# Sheet2.net
KiCad netlist of a schematic drawn in Altium Designer
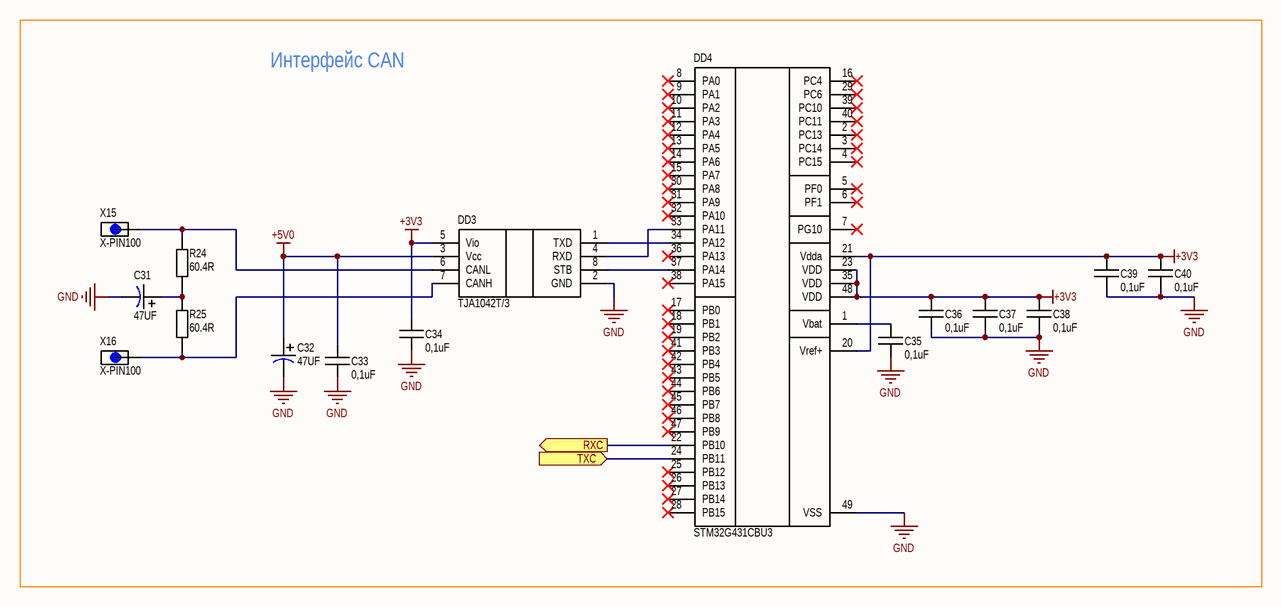
[diagram p0: Sheet2.SchDoc]

(export (version "E")
  (design (tool "Eeschema 10.0.6"))
  (components
    (comp (ref "C31")
      (value "47UF")
      (footprint "B1411_3528")
      (description "CP1411B 47UF 6V3")
      (fields
        (field (name "PART NUMBER") "SMD CAP TANTAL 47uF ±10% 6V3 1411B")
        (field (name "ADDED_BY") "ridel_av@teslatec.ru")
      )
      (libsource (lib "81801_1") (part "CP1411B-47UF"))
    )
    (comp (ref "C32")
      (value "47UF")
      (footprint "B1411_3528")
      (description "CP1411B 47UF 6V3")
      (fields
        (field (name "PART NUMBER") "SMD CAP TANTAL 47uF ±10% 6V3 1411B")
        (field (name "ADDED_BY") "ridel_av@teslatec.ru")
      )
      (libsource (lib "81801_1") (part "CP1411B-47UF"))
    )
    (comp (ref "C33")
      (value "0,1uF")
      (footprint "0805C")
      (description "C0805 0,1uF")
      (fields
        (field (name "PART NUMBER") "SMD CAP CER 0.1uF ±10% 25V X7R 0805")
        (field (name "ADDED_BY") "ridel_av@teslatec.ru")
      )
      (libsource (lib "81801_1") (part "C0805-0,1uF"))
    )
    (comp (ref "C34")
      (value "0,1uF")
      (footprint "0805C")
      (description "C0805 0,1uF")
      (fields
        (field (name "PART NUMBER") "SMD CAP CER 0.1uF ±10% 25V X7R 0805")
        (field (name "ADDED_BY") "ridel_av@teslatec.ru")
      )
      (libsource (lib "81801_1") (part "C0805-0,1uF"))
    )
    (comp (ref "C35")
      (value "0,1uF")
      (footprint "0805C")
      (description "C0805 0,1uF")
      (fields
        (field (name "PART NUMBER") "SMD CAP CER 0.1uF ±10% 25V X7R 0805")
        (field (name "ADDED_BY") "ridel_av@teslatec.ru")
      )
      (libsource (lib "81801_1") (part "C0805-0,1uF"))
    )
    (comp (ref "C36")
      (value "0,1uF")
      (footprint "0805C")
      (description "C0805 0,1uF")
      (fields
        (field (name "PART NUMBER") "SMD CAP CER 0.1uF ±10% 25V X7R 0805")
        (field (name "ADDED_BY") "ridel_av@teslatec.ru")
      )
      (libsource (lib "81801_1") (part "C0805-0,1uF"))
    )
    (comp (ref "C37")
      (value "0,1uF")
      (footprint "0805C")
      (description "C0805 0,1uF")
      (fields
        (field (name "PART NUMBER") "SMD CAP CER 0.1uF ±10% 25V X7R 0805")
        (field (name "ADDED_BY") "ridel_av@teslatec.ru")
      )
      (libsource (lib "81801_1") (part "C0805-0,1uF"))
    )
    (comp (ref "C38")
      (value "0,1uF")
      (footprint "0805C")
      (description "C0805 0,1uF")
      (fields
        (field (name "PART NUMBER") "SMD CAP CER 0.1uF ±10% 25V X7R 0805")
        (field (name "ADDED_BY") "ridel_av@teslatec.ru")
      )
      (libsource (lib "81801_1") (part "C0805-0,1uF"))
    )
    (comp (ref "C39")
      (value "0,1uF")
      (footprint "0805C")
      (description "C0805 0,1uF")
      (fields
        (field (name "PART NUMBER") "SMD CAP CER 0.1uF ±10% 25V X7R 0805")
        (field (name "ADDED_BY") "ridel_av@teslatec.ru")
      )
      (libsource (lib "81801_1") (part "C0805-0,1uF"))
    )
    (comp (ref "C40")
      (value "0,1uF")
      (footprint "0805C")
      (description "C0805 0,1uF")
      (fields
        (field (name "PART NUMBER") "SMD CAP CER 0.1uF ±10% 25V X7R 0805")
        (field (name "ADDED_BY") "ridel_av@teslatec.ru")
      )
      (libsource (lib "81801_1") (part "C0805-0,1uF"))
    )
    (comp (ref "DD3")
      (value "TJA1042T/3")
      (footprint "SOIC-8")
      (description "High-speed CAN transceiver with Standby mode")
      (fields (field (name "ADDED_BY") "dolgopolova_ia@teslatec.ru"))
      (libsource (lib "81801_1") (part "TJA1042T/3"))
    )
    (comp (ref "DD4")
      (value "STM32G431CBU3")
      (footprint "TQFP-64")
      (description "Arm Cortex-M4 32b MCU+FPU, 170 MHz / 213 DMIPS, 128 KB Flash")
      (fields (field (name "ADDED_BY") "ridel_av@teslatec.ru"))
      (libsource (lib "81801_1") (part "STM32G431CBU3"))
    )
    (comp (ref "R24")
      (value "60.4R")
      (footprint "R0805")
      (description "R0805 SMD 60.4R OHM 1% ±100ppm/°C")
      (fields
        (field (name "PART NUMBER") "SMD RES 60.4 OHM 1% ±100ppm/°C 0805")
        (field (name "ADDED_BY") "ridel_av@teslatec.ru")
      )
      (libsource (lib "81801_1") (part "R0805-60.4R"))
    )
    (comp (ref "R25")
      (value "60.4R")
      (footprint "R0805")
      (description "R0805 SMD 60.4R OHM 1% ±100ppm/°C")
      (fields
        (field (name "PART NUMBER") "SMD RES 60.4 OHM 1% ±100ppm/°C 0805")
        (field (name "ADDED_BY") "ridel_av@teslatec.ru")
      )
      (libsource (lib "81801_1") (part "R0805-60.4R"))
    )
    (comp (ref "X15")
      (value "X-PIN100")
      (footprint "Xpin100")
      (fields (field (name "ADDED_BY") "ridel_av@teslatec.ru"))
      (libsource (lib "81801_1") (part "X-PIN100"))
    )
    (comp (ref "X16")
      (value "X-PIN100")
      (footprint "Xpin100")
      (fields (field (name "ADDED_BY") "ridel_av@teslatec.ru"))
      (libsource (lib "81801_1") (part "X-PIN100"))
    )
  )
  (nets
    (net (code "1") (name "+3V3") (class "Default")
      (node (ref "C34") (pin "1") (pinfunction "1_1") (pintype "passive"))
      (node (ref "C36") (pin "1") (pinfunction "1_1") (pintype "passive"))
      (node (ref "C37") (pin "1") (pinfunction "1_1") (pintype "passive"))
      (node (ref "C38") (pin "1") (pinfunction "1_1") (pintype "passive"))
      (node (ref "C39") (pin "1") (pinfunction "1_1") (pintype "passive"))
      (node (ref "C40") (pin "1") (pinfunction "1_1") (pintype "passive"))
      (node (ref "DD3") (pin "5") (pinfunction "Vio_5") (pintype "passive"))
      (node (ref "DD4") (pin "20") (pinfunction "Vref+_20") (pintype "passive"))
      (node (ref "DD4") (pin "21") (pinfunction "Vdda_21") (pintype "passive"))
      (node (ref "DD4") (pin "23") (pinfunction "VDD_23") (pintype "passive"))
      (node (ref "DD4") (pin "35") (pinfunction "VDD_35") (pintype "passive"))
      (node (ref "DD4") (pin "48") (pinfunction "VDD_48") (pintype "passive"))
    )
    (net (code "2") (name "+5V0") (class "Default")
      (node (ref "C32") (pin "1") (pinfunction "1_1") (pintype "passive"))
      (node (ref "C33") (pin "1") (pinfunction "1_1") (pintype "passive"))
      (node (ref "DD3") (pin "3") (pinfunction "Vcc_3") (pintype "passive"))
    )
    (net (code "3") (name "/RXC") (class "Default")
      (node (ref "DD4") (pin "22") (pinfunction "PB10_22") (pintype "passive"))
    )
    (net (code "4") (name "/TXC") (class "Default")
      (node (ref "DD4") (pin "24") (pinfunction "PB11_24") (pintype "passive"))
    )
    (net (code "5") (name "GND") (class "Default")
      (node (ref "C31") (pin "2") (pinfunction "2_2") (pintype "passive"))
      (node (ref "C32") (pin "2") (pinfunction "2_2") (pintype "passive"))
      (node (ref "C33") (pin "2") (pinfunction "2_2") (pintype "passive"))
      (node (ref "C34") (pin "2") (pinfunction "2_2") (pintype "passive"))
      (node (ref "C35") (pin "2") (pinfunction "2_2") (pintype "passive"))
      (node (ref "C36") (pin "2") (pinfunction "2_2") (pintype "passive"))
      (node (ref "C37") (pin "2") (pinfunction "2_2") (pintype "passive"))
      (node (ref "C38") (pin "2") (pinfunction "2_2") (pintype "passive"))
      (node (ref "C39") (pin "2") (pinfunction "2_2") (pintype "passive"))
      (node (ref "C40") (pin "2") (pinfunction "2_2") (pintype "passive"))
      (node (ref "DD3") (pin "2") (pinfunction "GND_2") (pintype "passive"))
      (node (ref "DD4") (pin "49") (pinfunction "VSS_49") (pintype "passive"))
    )
    (net (code "6") (name "Net-(C31-Pad1)") (class "Default")
      (node (ref "C31") (pin "1") (pinfunction "1_1") (pintype "passive"))
      (node (ref "R24") (pin "1") (pinfunction "1_1") (pintype "passive"))
      (node (ref "R25") (pin "2") (pinfunction "2_2") (pintype "passive"))
    )
    (net (code "7") (name "Net-(DD3-CANH)") (class "Default")
      (node (ref "DD3") (pin "7") (pinfunction "CANH_7") (pintype "passive"))
      (node (ref "R25") (pin "1") (pinfunction "1_1") (pintype "passive"))
      (node (ref "X16") (pin "1") (pintype "passive"))
    )
    (net (code "8") (name "Net-(DD3-CANL)") (class "Default")
      (node (ref "DD3") (pin "6") (pinfunction "CANL_6") (pintype "passive"))
      (node (ref "R24") (pin "2") (pinfunction "2_2") (pintype "passive"))
      (node (ref "X15") (pin "1") (pintype "passive"))
    )
    (net (code "9") (name "Net-(DD3-RXD)") (class "Default")
      (node (ref "DD3") (pin "4") (pinfunction "RXD_4") (pintype "passive"))
      (node (ref "DD4") (pin "33") (pinfunction "PA11_33") (pintype "passive"))
    )
    (net (code "10") (name "Net-(DD3-STB)") (class "Default")
      (node (ref "DD3") (pin "8") (pinfunction "STB_8") (pintype "passive"))
      (node (ref "DD4") (pin "37") (pinfunction "PA14_37") (pintype "passive"))
    )
    (net (code "11") (name "Net-(DD3-TXD)") (class "Default")
      (node (ref "DD3") (pin "1") (pinfunction "TXD_1") (pintype "passive"))
      (node (ref "DD4") (pin "34") (pinfunction "PA12_34") (pintype "passive"))
    )
    (net (code "12") (name "Net-(DD4-Vbat)") (class "Default")
      (node (ref "C35") (pin "1") (pinfunction "1_1") (pintype "passive"))
      (node (ref "DD4") (pin "1") (pinfunction "Vbat_1") (pintype "passive"))
    )
    (net (code "13") (name "unconnected-(DD4-PA0-Pad8)") (class "Default")
      (node (ref "DD4") (pin "8") (pinfunction "PA0_8") (pintype "passive+no_connect"))
    )
    (net (code "14") (name "unconnected-(DD4-PA1-Pad9)") (class "Default")
      (node (ref "DD4") (pin "9") (pinfunction "PA1_9") (pintype "passive+no_connect"))
    )
    (net (code "15") (name "unconnected-(DD4-PA2-Pad10)") (class "Default")
      (node (ref "DD4") (pin "10") (pinfunction "PA2_10") (pintype "passive+no_connect"))
    )
    (net (code "16") (name "unconnected-(DD4-PA3-Pad11)") (class "Default")
      (node (ref "DD4") (pin "11") (pinfunction "PA3_11") (pintype "passive+no_connect"))
    )
    (net (code "17") (name "unconnected-(DD4-PA4-Pad12)") (class "Default")
      (node (ref "DD4") (pin "12") (pinfunction "PA4_12") (pintype "passive+no_connect"))
    )
    (net (code "18") (name "unconnected-(DD4-PA5-Pad13)") (class "Default")
      (node (ref "DD4") (pin "13") (pinfunction "PA5_13") (pintype "passive+no_connect"))
    )
    (net (code "19") (name "unconnected-(DD4-PA6-Pad14)") (class "Default")
      (node (ref "DD4") (pin "14") (pinfunction "PA6_14") (pintype "passive+no_connect"))
    )
    (net (code "20") (name "unconnected-(DD4-PA7-Pad15)") (class "Default")
      (node (ref "DD4") (pin "15") (pinfunction "PA7_15") (pintype "passive+no_connect"))
    )
    (net (code "21") (name "unconnected-(DD4-PA8-Pad30)") (class "Default")
      (node (ref "DD4") (pin "30") (pinfunction "PA8_30") (pintype "passive+no_connect"))
    )
    (net (code "22") (name "unconnected-(DD4-PA9-Pad31)") (class "Default")
      (node (ref "DD4") (pin "31") (pinfunction "PA9_31") (pintype "passive+no_connect"))
    )
    (net (code "23") (name "unconnected-(DD4-PA10-Pad32)") (class "Default")
      (node (ref "DD4") (pin "32") (pinfunction "PA10_32") (pintype "passive+no_connect"))
    )
    (net (code "24") (name "unconnected-(DD4-PA13-Pad36)") (class "Default")
      (node (ref "DD4") (pin "36") (pinfunction "PA13_36") (pintype "passive+no_connect"))
    )
    (net (code "25") (name "unconnected-(DD4-PA15-Pad38)") (class "Default")
      (node (ref "DD4") (pin "38") (pinfunction "PA15_38") (pintype "passive+no_connect"))
    )
    (net (code "26") (name "unconnected-(DD4-PB0-Pad17)") (class "Default")
      (node (ref "DD4") (pin "17") (pinfunction "PB0_17") (pintype "passive+no_connect"))
    )
    (net (code "27") (name "unconnected-(DD4-PB1-Pad18)") (class "Default")
      (node (ref "DD4") (pin "18") (pinfunction "PB1_18") (pintype "passive+no_connect"))
    )
    (net (code "28") (name "unconnected-(DD4-PB2-Pad19)") (class "Default")
      (node (ref "DD4") (pin "19") (pinfunction "PB2_19") (pintype "passive+no_connect"))
    )
    (net (code "29") (name "unconnected-(DD4-PB3-Pad41)") (class "Default")
      (node (ref "DD4") (pin "41") (pinfunction "PB3_41") (pintype "passive+no_connect"))
    )
    (net (code "30") (name "unconnected-(DD4-PB4-Pad42)") (class "Default")
      (node (ref "DD4") (pin "42") (pinfunction "PB4_42") (pintype "passive+no_connect"))
    )
    (net (code "31") (name "unconnected-(DD4-PB5-Pad43)") (class "Default")
      (node (ref "DD4") (pin "43") (pinfunction "PB5_43") (pintype "passive+no_connect"))
    )
    (net (code "32") (name "unconnected-(DD4-PB6-Pad44)") (class "Default")
      (node (ref "DD4") (pin "44") (pinfunction "PB6_44") (pintype "passive+no_connect"))
    )
    (net (code "33") (name "unconnected-(DD4-PB7-Pad45)") (class "Default")
      (node (ref "DD4") (pin "45") (pinfunction "PB7_45") (pintype "passive+no_connect"))
    )
    (net (code "34") (name "unconnected-(DD4-PB8-Pad46)") (class "Default")
      (node (ref "DD4") (pin "46") (pinfunction "PB8_46") (pintype "passive+no_connect"))
    )
    (net (code "35") (name "unconnected-(DD4-PB9-Pad47)") (class "Default")
      (node (ref "DD4") (pin "47") (pinfunction "PB9_47") (pintype "passive+no_connect"))
    )
    (net (code "36") (name "unconnected-(DD4-PB12-Pad25)") (class "Default")
      (node (ref "DD4") (pin "25") (pinfunction "PB12_25") (pintype "passive+no_connect"))
    )
    (net (code "37") (name "unconnected-(DD4-PB13-Pad26)") (class "Default")
      (node (ref "DD4") (pin "26") (pinfunction "PB13_26") (pintype "passive+no_connect"))
    )
    (net (code "38") (name "unconnected-(DD4-PB14-Pad27)") (class "Default")
      (node (ref "DD4") (pin "27") (pinfunction "PB14_27") (pintype "passive+no_connect"))
    )
    (net (code "39") (name "unconnected-(DD4-PB15-Pad28)") (class "Default")
      (node (ref "DD4") (pin "28") (pinfunction "PB15_28") (pintype "passive+no_connect"))
    )
    (net (code "40") (name "unconnected-(DD4-PC4-Pad16)") (class "Default")
      (node (ref "DD4") (pin "16") (pinfunction "PC4_16") (pintype "passive+no_connect"))
    )
    (net (code "41") (name "unconnected-(DD4-PC6-Pad29)") (class "Default")
      (node (ref "DD4") (pin "29") (pinfunction "PC6_29") (pintype "passive+no_connect"))
    )
    (net (code "42") (name "unconnected-(DD4-PC10-Pad39)") (class "Default")
      (node (ref "DD4") (pin "39") (pinfunction "PC10_39") (pintype "passive+no_connect"))
    )
    (net (code "43") (name "unconnected-(DD4-PC11-Pad40)") (class "Default")
      (node (ref "DD4") (pin "40") (pinfunction "PC11_40") (pintype "passive+no_connect"))
    )
    (net (code "44") (name "unconnected-(DD4-PC13-Pad2)") (class "Default")
      (node (ref "DD4") (pin "2") (pinfunction "PC13_2") (pintype "passive+no_connect"))
    )
    (net (code "45") (name "unconnected-(DD4-PC14-Pad3)") (class "Default")
      (node (ref "DD4") (pin "3") (pinfunction "PC14_3") (pintype "passive+no_connect"))
    )
    (net (code "46") (name "unconnected-(DD4-PC15-Pad4)") (class "Default")
      (node (ref "DD4") (pin "4") (pinfunction "PC15_4") (pintype "passive+no_connect"))
    )
    (net (code "47") (name "unconnected-(DD4-PF0-Pad5)") (class "Default")
      (node (ref "DD4") (pin "5") (pinfunction "PF0_5") (pintype "passive+no_connect"))
    )
    (net (code "48") (name "unconnected-(DD4-PF1-Pad6)") (class "Default")
      (node (ref "DD4") (pin "6") (pinfunction "PF1_6") (pintype "passive+no_connect"))
    )
    (net (code "49") (name "unconnected-(DD4-PG10-Pad7)") (class "Default")
      (node (ref "DD4") (pin "7") (pinfunction "PG10_7") (pintype "passive+no_connect"))
    )
  )
)
